# 3_5mm_RCA_breakout.net
KiCad netlist of a schematic drawn in EAGLE
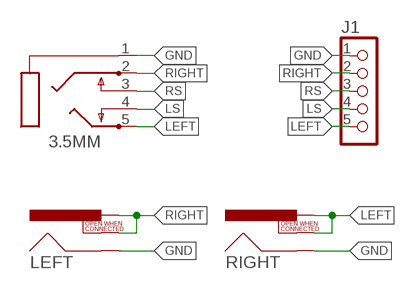
[diagram p0: schematic, sheet 1]

(export (version "E")
  (design (tool "Eeschema 10.0.6"))
  (components
    (comp (ref "3.5MM")
      (value "STEREOJACK")
      (footprint "eagle-import:STX3100")
      (libsource (lib "eagle-import") (part "STEREOJACK"))
    )
    (comp (ref "J1")
      (value "CON_HEADER_1X05-PTH")
      (footprint "eagle-import:M1X5")
      (libsource (lib "eagle-import") (part "CON_HEADER_1X05-PTH"))
    )
    (comp (ref "LEFT")
      (value "RCA")
      (footprint "eagle-import:RCA")
      (libsource (lib "eagle-import") (part "RCA"))
    )
    (comp (ref "RIGHT")
      (value "RCA")
      (footprint "eagle-import:RCA")
      (libsource (lib "eagle-import") (part "RCA"))
    )
  )
  (nets
    (net (code "1") (name "GND") (class "Default")
      (node (ref "3.5MM") (pin "1") (pinfunction "1_1") (pintype "passive"))
      (node (ref "J1") (pin "1") (pinfunction "1_1") (pintype "bidirectional"))
      (node (ref "LEFT") (pin "SHELL") (pinfunction "SHELL_SHELL") (pintype "bidirectional"))
      (node (ref "RIGHT") (pin "SHELL") (pinfunction "SHELL_SHELL") (pintype "bidirectional"))
    )
    (net (code "2") (name "LEFT") (class "Default")
      (node (ref "3.5MM") (pin "5") (pinfunction "5_5") (pintype "passive"))
      (node (ref "J1") (pin "5") (pinfunction "5_5") (pintype "bidirectional"))
      (node (ref "RIGHT") (pin "PIN") (pinfunction "PIN_PIN") (pintype "bidirectional"))
      (node (ref "RIGHT") (pin "SWITCH") (pinfunction "SWITCH_SWITCH") (pintype "bidirectional"))
    )
    (net (code "3") (name "LS") (class "Default")
      (node (ref "3.5MM") (pin "4") (pinfunction "4_4") (pintype "passive"))
      (node (ref "J1") (pin "4") (pinfunction "4_4") (pintype "bidirectional"))
    )
    (net (code "4") (name "RIGHT") (class "Default")
      (node (ref "3.5MM") (pin "2") (pinfunction "2_2") (pintype "passive"))
      (node (ref "J1") (pin "2") (pinfunction "2_2") (pintype "bidirectional"))
      (node (ref "LEFT") (pin "PIN") (pinfunction "PIN_PIN") (pintype "bidirectional"))
      (node (ref "LEFT") (pin "SWITCH") (pinfunction "SWITCH_SWITCH") (pintype "bidirectional"))
    )
    (net (code "5") (name "RS") (class "Default")
      (node (ref "3.5MM") (pin "3") (pinfunction "3_3") (pintype "passive"))
      (node (ref "J1") (pin "3") (pinfunction "3_3") (pintype "bidirectional"))
    )
  )
)
